# Bank.net
KiCad netlist of a schematic drawn in Altium Designer
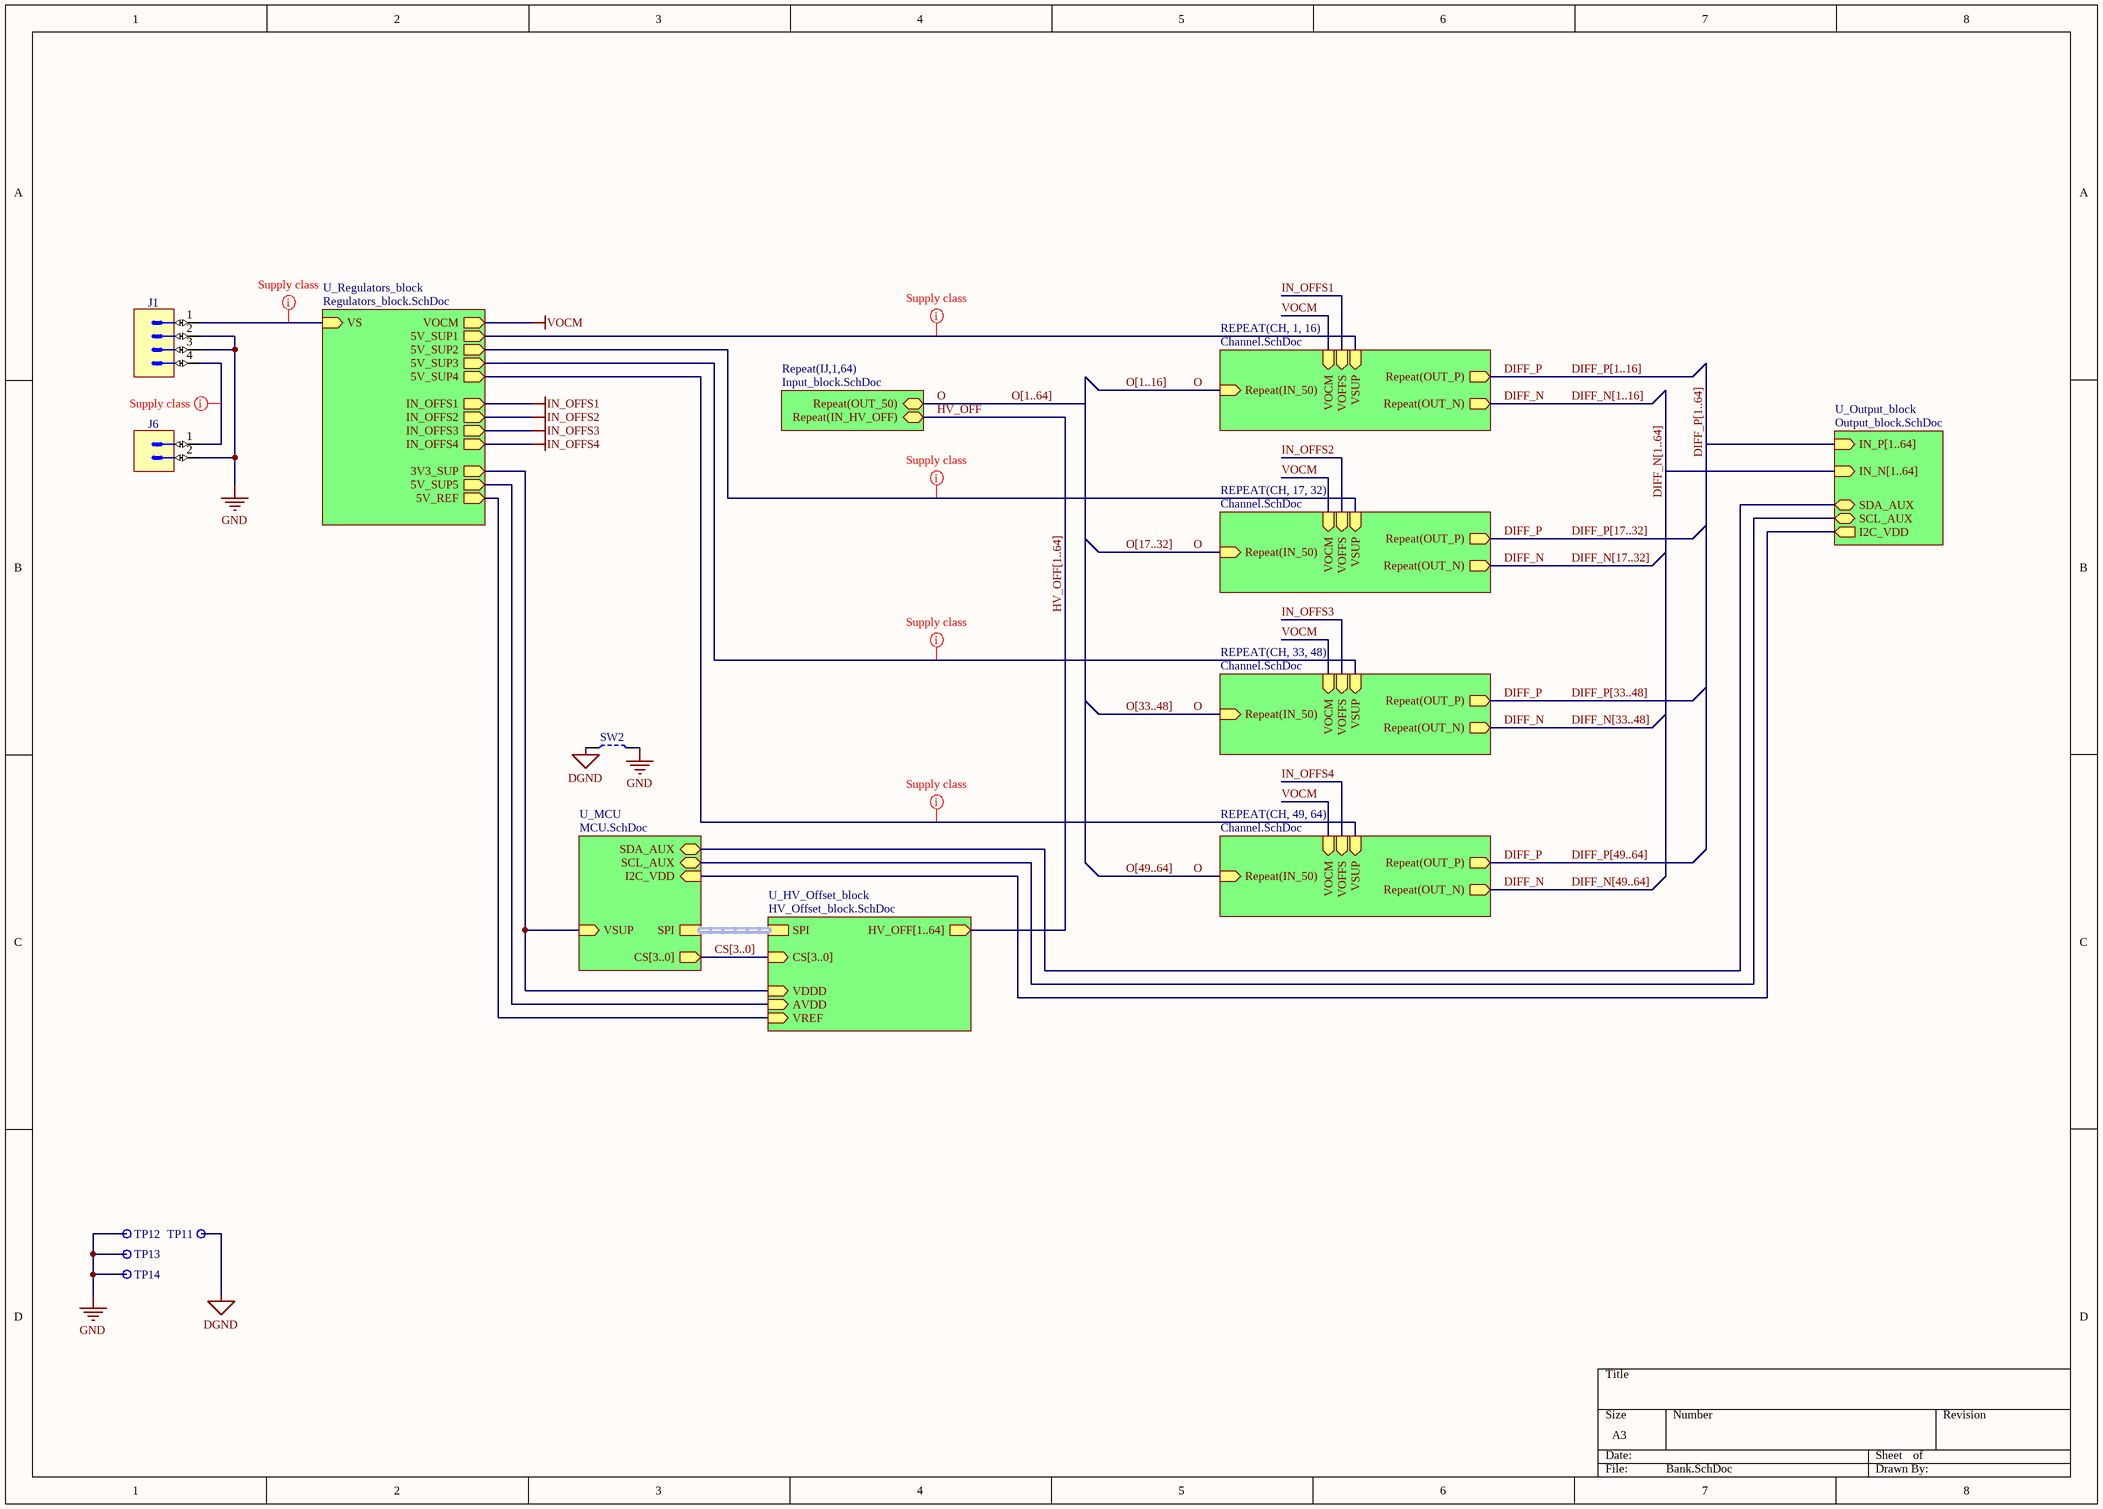
[diagram p0: Bank.SchDoc]

(export (version "E")
  (design (tool "Eeschema 10.0.6"))
  (components
    (comp (ref "J1")
      (value "Header 4")
      (footprint "WURTH_691 313 410 004")
      (description "Connector 4 Male")
      (fields
        (field (name "PART NUMBER") "WURTH_691 313 410 004")
        (field (name "MANUFACTURER") "WURTH ELEKTRONIK")
        (field (name "AUTHOR") "CERN DEM MR")
      )
      (libsource (lib "Connectors") (part "Connector 4 Male"))
    )
    (comp (ref "J6")
      (value "KK®")
      (footprint "MOLEX_22-04-1021")
      (description "Connector 2 Male")
      (fields
        (field (name "PART NUMBER") "MOLEX_22-04-1021")
        (field (name "MANUFACTURER") "MOLEX")
        (field (name "AUTHOR") "CERN DEM JLC")
      )
      (libsource (lib "Connectors") (part "Connector 2 Male"))
    )
    (comp (ref "SW2")
      (value "Switch")
      (footprint "JUMPSMD0805_G50")
      (description "2 SMD Pads for Bound by Solder  Drop")
      (fields
        (field (name "PART NUMBER") "JUMPSMD0805_G50")
        (field (name "MANUFACTURER") "None")
        (field (name "AUTHOR") "CERN DEM JLC")
      )
      (libsource (lib "Eletro-mechanical") (part "SMD Solder Jumper"))
    )
    (comp (ref "TP11")
      (value "Test Point")
      (footprint "VERO_20-313145")
      (fields
        (field (name "PART NUMBER") "VERO_20-313145")
        (field (name "MANUFACTURER") "VERO TECHNOLOGIES")
        (field (name "MANUFACTURER PART NUMBER") "20-313145")
        (field (name "AUTHOR") "CERN DEM JLC")
      )
      (libsource (lib "Connectors") (part "Test Point"))
    )
    (comp (ref "TP12")
      (value "Test Point")
      (footprint "VERO_20-313145")
      (fields
        (field (name "PART NUMBER") "VERO_20-313145")
        (field (name "MANUFACTURER") "VERO TECHNOLOGIES")
        (field (name "MANUFACTURER PART NUMBER") "20-313145")
        (field (name "AUTHOR") "CERN DEM JLC")
      )
      (libsource (lib "Connectors") (part "Test Point"))
    )
    (comp (ref "TP13")
      (value "Test Point")
      (footprint "VERO_20-313145")
      (fields
        (field (name "PART NUMBER") "VERO_20-313145")
        (field (name "MANUFACTURER") "VERO TECHNOLOGIES")
        (field (name "MANUFACTURER PART NUMBER") "20-313145")
        (field (name "AUTHOR") "CERN DEM JLC")
      )
      (libsource (lib "Connectors") (part "Test Point"))
    )
    (comp (ref "TP14")
      (value "Test Point")
      (footprint "VERO_20-313145")
      (fields
        (field (name "PART NUMBER") "VERO_20-313145")
        (field (name "MANUFACTURER") "VERO TECHNOLOGIES")
        (field (name "MANUFACTURER PART NUMBER") "20-313145")
        (field (name "AUTHOR") "CERN DEM JLC")
      )
      (libsource (lib "Connectors") (part "Test Point"))
    )
  )
  (nets
    (net (code "293") (name "/VS") (class "Default")
      (node (ref "J1") (pin "1") (pinfunction "1_1") (pintype "bidirectional"))
    )
    (net (code "294") (name "DGND") (class "Default")
      (node (ref "SW2") (pin "1") (pinfunction "1_1") (pintype "passive"))
      (node (ref "TP11") (pin "1") (pinfunction "1_1") (pintype "bidirectional"))
    )
    (net (code "295") (name "GND") (class "Default")
      (node (ref "J1") (pin "2") (pinfunction "2_2") (pintype "bidirectional"))
      (node (ref "J1") (pin "3") (pinfunction "3_3") (pintype "bidirectional"))
      (node (ref "J6") (pin "2") (pinfunction "2_2") (pintype "bidirectional"))
      (node (ref "SW2") (pin "2") (pinfunction "2_2") (pintype "passive"))
      (node (ref "TP12") (pin "1") (pinfunction "1_1") (pintype "bidirectional"))
      (node (ref "TP13") (pin "1") (pinfunction "1_1") (pintype "bidirectional"))
      (node (ref "TP14") (pin "1") (pinfunction "1_1") (pintype "bidirectional"))
    )
    (net (code "300") (name "Net-(J1-Pad4)") (class "Default")
      (node (ref "J1") (pin "4") (pinfunction "4_4") (pintype "bidirectional"))
      (node (ref "J6") (pin "1") (pinfunction "1_1") (pintype "bidirectional"))
    )
  )
)
